# 8X8_MATRIX_LED.net
KiCad netlist of a schematic drawn in Altium Designer
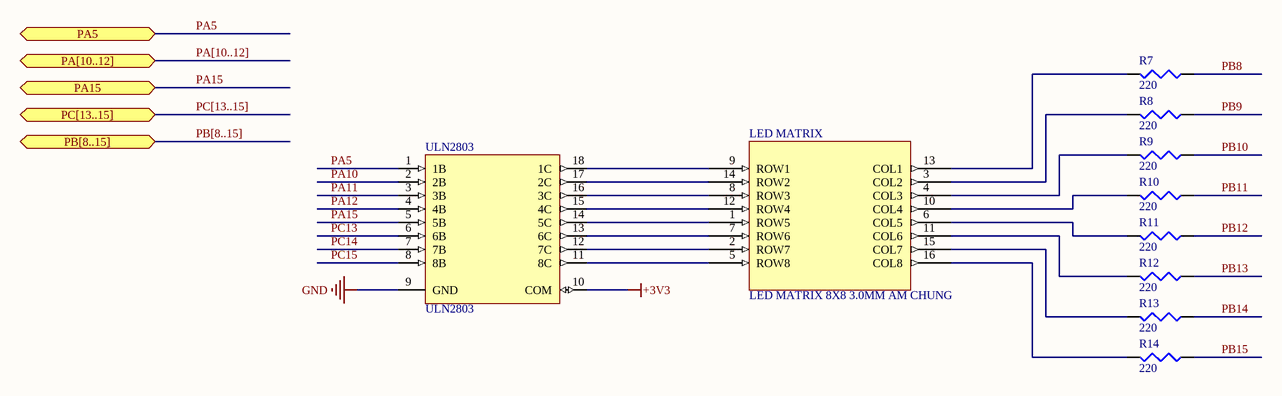
[diagram p0: 8X8_MATRIX_LED.SchDoc]

(export (version "E")
  (design (tool "Eeschema 10.0.6"))
  (components
    (comp (ref "LED MATRIX")
      (value "LED MATRIX 8X8 3.0MM AM CHUNG")
      (footprint "MATRIX LED 8X8 3.0mm")
      (description "https://www.thegioiic.com/1088as-led-ma-tran-8x8-am-chung-mau-do-diem-dot-3-0mm")
      (fields (field (name "JLCPCB PART #") "C2980922"))
      (libsource (lib "Ho Chi Minh City University of Technology") (part "D?"))
    )
    (comp (ref "R7")
      (value "220")
      (footprint "0805 (2012 Metric)")
      (description "Oreki")
      (libsource (lib "Ho Chi Minh City University of Technology") (part "RES-2"))
    )
    (comp (ref "R8")
      (value "220")
      (footprint "0805 (2012 Metric)")
      (description "Oreki")
      (libsource (lib "Ho Chi Minh City University of Technology") (part "RES-2"))
    )
    (comp (ref "R9")
      (value "220")
      (footprint "0805 (2012 Metric)")
      (description "Oreki")
      (libsource (lib "Ho Chi Minh City University of Technology") (part "RES-2"))
    )
    (comp (ref "R10")
      (value "220")
      (footprint "0805 (2012 Metric)")
      (description "Oreki")
      (libsource (lib "Ho Chi Minh City University of Technology") (part "RES-2"))
    )
    (comp (ref "R11")
      (value "220")
      (footprint "0805 (2012 Metric)")
      (description "Oreki")
      (libsource (lib "Ho Chi Minh City University of Technology") (part "RES-2"))
    )
    (comp (ref "R12")
      (value "220")
      (footprint "0805 (2012 Metric)")
      (description "Oreki")
      (libsource (lib "Ho Chi Minh City University of Technology") (part "RES-2"))
    )
    (comp (ref "R13")
      (value "220")
      (footprint "0805 (2012 Metric)")
      (description "Oreki")
      (libsource (lib "Ho Chi Minh City University of Technology") (part "RES-2"))
    )
    (comp (ref "R14")
      (value "220")
      (footprint "0805 (2012 Metric)")
      (description "Oreki")
      (libsource (lib "Ho Chi Minh City University of Technology") (part "RES-2"))
    )
    (comp (ref "ULN2803")
      (value "ULN2803")
      (footprint "SOP18 - UMW")
      (description "LLQT")
      (fields (field (name "JLCPCB PART #") "C5252904"))
      (libsource (lib "Ho Chi Minh City University of Technology") (part "U?"))
    )
  )
  (nets
    (net (code "1") (name "+3V3") (class "Default")
      (node (ref "ULN2803") (pin "10") (pinfunction "COM_10") (pintype "bidirectional"))
    )
    (net (code "2") (name "/PA5") (class "Default")
      (node (ref "ULN2803") (pin "1") (pinfunction "1B_1") (pintype "input"))
    )
    (net (code "3") (name "/PA10") (class "Default")
      (node (ref "ULN2803") (pin "2") (pinfunction "2B_2") (pintype "input"))
    )
    (net (code "4") (name "/PA11") (class "Default")
      (node (ref "ULN2803") (pin "3") (pinfunction "3B_3") (pintype "input"))
    )
    (net (code "5") (name "/PA12") (class "Default")
      (node (ref "ULN2803") (pin "4") (pinfunction "4B_4") (pintype "input"))
    )
    (net (code "6") (name "/PA15") (class "Default")
      (node (ref "ULN2803") (pin "5") (pinfunction "5B_5") (pintype "input"))
    )
    (net (code "8") (name "/PB8") (class "Default")
      (node (ref "R7") (pin "1") (pinfunction "1_1") (pintype "passive"))
    )
    (net (code "9") (name "/PB9") (class "Default")
      (node (ref "R8") (pin "1") (pinfunction "1_1") (pintype "passive"))
    )
    (net (code "10") (name "/PB10") (class "Default")
      (node (ref "R9") (pin "1") (pinfunction "1_1") (pintype "passive"))
    )
    (net (code "11") (name "/PB11") (class "Default")
      (node (ref "R10") (pin "1") (pinfunction "1_1") (pintype "passive"))
    )
    (net (code "12") (name "/PB12") (class "Default")
      (node (ref "R11") (pin "1") (pinfunction "1_1") (pintype "passive"))
    )
    (net (code "13") (name "/PB13") (class "Default")
      (node (ref "R12") (pin "1") (pinfunction "1_1") (pintype "passive"))
    )
    (net (code "14") (name "/PB14") (class "Default")
      (node (ref "R13") (pin "1") (pinfunction "1_1") (pintype "passive"))
    )
    (net (code "15") (name "/PB15") (class "Default")
      (node (ref "R14") (pin "1") (pinfunction "1_1") (pintype "passive"))
    )
    (net (code "17") (name "/PC13") (class "Default")
      (node (ref "ULN2803") (pin "6") (pinfunction "6B_6") (pintype "input"))
    )
    (net (code "18") (name "/PC14") (class "Default")
      (node (ref "ULN2803") (pin "7") (pinfunction "7B_7") (pintype "input"))
    )
    (net (code "19") (name "/PC15") (class "Default")
      (node (ref "ULN2803") (pin "8") (pinfunction "8B_8") (pintype "input"))
    )
    (net (code "21") (name "GND") (class "Default")
      (node (ref "ULN2803") (pin "9") (pinfunction "GND_9") (pintype "power_in"))
    )
    (net (code "22") (name "Net-(LED MATRIX-COL1)") (class "Default")
      (node (ref "LED MATRIX") (pin "13") (pinfunction "COL1_13") (pintype "output"))
      (node (ref "R7") (pin "2") (pinfunction "2_2") (pintype "passive"))
    )
    (net (code "23") (name "Net-(LED MATRIX-COL2)") (class "Default")
      (node (ref "LED MATRIX") (pin "3") (pinfunction "COL2_3") (pintype "output"))
      (node (ref "R8") (pin "2") (pinfunction "2_2") (pintype "passive"))
    )
    (net (code "24") (name "Net-(LED MATRIX-COL3)") (class "Default")
      (node (ref "LED MATRIX") (pin "4") (pinfunction "COL3_4") (pintype "output"))
      (node (ref "R9") (pin "2") (pinfunction "2_2") (pintype "passive"))
    )
    (net (code "25") (name "Net-(LED MATRIX-COL4)") (class "Default")
      (node (ref "LED MATRIX") (pin "10") (pinfunction "COL4_10") (pintype "output"))
      (node (ref "R10") (pin "2") (pinfunction "2_2") (pintype "passive"))
    )
    (net (code "26") (name "Net-(LED MATRIX-COL5)") (class "Default")
      (node (ref "LED MATRIX") (pin "6") (pinfunction "COL5_6") (pintype "output"))
      (node (ref "R11") (pin "2") (pinfunction "2_2") (pintype "passive"))
    )
    (net (code "27") (name "Net-(LED MATRIX-COL6)") (class "Default")
      (node (ref "LED MATRIX") (pin "11") (pinfunction "COL6_11") (pintype "output"))
      (node (ref "R12") (pin "2") (pinfunction "2_2") (pintype "passive"))
    )
    (net (code "28") (name "Net-(LED MATRIX-COL7)") (class "Default")
      (node (ref "LED MATRIX") (pin "15") (pinfunction "COL7_15") (pintype "output"))
      (node (ref "R13") (pin "2") (pinfunction "2_2") (pintype "passive"))
    )
    (net (code "29") (name "Net-(LED MATRIX-COL8)") (class "Default")
      (node (ref "LED MATRIX") (pin "16") (pinfunction "COL8_16") (pintype "output"))
      (node (ref "R14") (pin "2") (pinfunction "2_2") (pintype "passive"))
    )
    (net (code "30") (name "Net-(LED MATRIX-ROW1)") (class "Default")
      (node (ref "LED MATRIX") (pin "9") (pinfunction "ROW1_9") (pintype "input"))
      (node (ref "ULN2803") (pin "18") (pinfunction "1C_18") (pintype "output"))
    )
    (net (code "31") (name "Net-(LED MATRIX-ROW2)") (class "Default")
      (node (ref "LED MATRIX") (pin "14") (pinfunction "ROW2_14") (pintype "input"))
      (node (ref "ULN2803") (pin "17") (pinfunction "2C_17") (pintype "output"))
    )
    (net (code "32") (name "Net-(LED MATRIX-ROW3)") (class "Default")
      (node (ref "LED MATRIX") (pin "8") (pinfunction "ROW3_8") (pintype "input"))
      (node (ref "ULN2803") (pin "16") (pinfunction "3C_16") (pintype "output"))
    )
    (net (code "33") (name "Net-(LED MATRIX-ROW4)") (class "Default")
      (node (ref "LED MATRIX") (pin "12") (pinfunction "ROW4_12") (pintype "input"))
      (node (ref "ULN2803") (pin "15") (pinfunction "4C_15") (pintype "output"))
    )
    (net (code "34") (name "Net-(LED MATRIX-ROW5)") (class "Default")
      (node (ref "LED MATRIX") (pin "1") (pinfunction "ROW5_1") (pintype "input"))
      (node (ref "ULN2803") (pin "14") (pinfunction "5C_14") (pintype "output"))
    )
    (net (code "35") (name "Net-(LED MATRIX-ROW6)") (class "Default")
      (node (ref "LED MATRIX") (pin "7") (pinfunction "ROW6_7") (pintype "input"))
      (node (ref "ULN2803") (pin "13") (pinfunction "6C_13") (pintype "output"))
    )
    (net (code "36") (name "Net-(LED MATRIX-ROW7)") (class "Default")
      (node (ref "LED MATRIX") (pin "2") (pinfunction "ROW7_2") (pintype "input"))
      (node (ref "ULN2803") (pin "12") (pinfunction "7C_12") (pintype "output"))
    )
    (net (code "37") (name "Net-(LED MATRIX-ROW8)") (class "Default")
      (node (ref "LED MATRIX") (pin "5") (pinfunction "ROW8_5") (pintype "input"))
      (node (ref "ULN2803") (pin "11") (pinfunction "8C_11") (pintype "output"))
    )
  )
)
